# 05_Uart_Bluetooth.net
KiCad netlist of a schematic drawn in Altium Designer
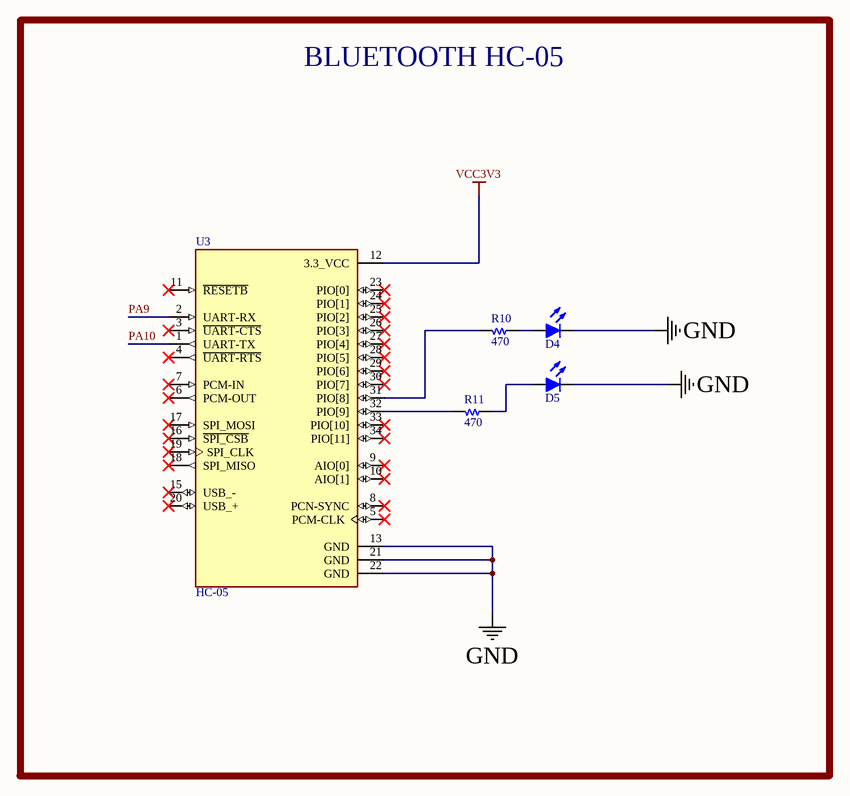
[diagram p0: 05_Uart_Bluetooth.SchDoc]

(export (version "E")
  (design (tool "Eeschema 10.0.6"))
  (components
    (comp (ref "D4")
      (value "Led")
      (footprint "Led 0805")
      (description "Typical LED")
      (libsource (lib "led") (part "Led"))
    )
    (comp (ref "D5")
      (value "Led")
      (footprint "Led 0805")
      (description "Typical LED")
      (libsource (lib "led") (part "Led"))
    )
    (comp (ref "R10")
      (value "470")
      (footprint "R 0805")
      (description "Resistor")
      (libsource (lib "chipfc_libs") (part "Resistor"))
    )
    (comp (ref "R11")
      (value "470")
      (footprint "R 0805")
      (description "Resistor")
      (libsource (lib "chipfc_libs") (part "Resistor"))
    )
    (comp (ref "U3")
      (value "HC-05")
      (footprint "XCVR_HC-05")
      (description "Bluetooth to Serial Port Module")
      (libsource (lib "HC-05") (part "HC-05"))
    )
  )
  (nets
    (net (code "1") (name "/PA9") (class "Default")
      (node (ref "U3") (pin "2") (pinfunction "UART-RX_2") (pintype "input"))
    )
    (net (code "2") (name "/PA10") (class "Default")
      (node (ref "U3") (pin "1") (pinfunction "UART-TX_1") (pintype "output"))
    )
    (net (code "3") (name "GND") (class "Default")
      (node (ref "D4") (pin "2") (pinfunction "K_2") (pintype "passive"))
      (node (ref "D5") (pin "2") (pinfunction "K_2") (pintype "passive"))
      (node (ref "U3") (pin "13") (pinfunction "GND_13") (pintype "power_in"))
      (node (ref "U3") (pin "21") (pinfunction "GND_21") (pintype "power_in"))
      (node (ref "U3") (pin "22") (pinfunction "GND_22") (pintype "power_in"))
    )
    (net (code "4") (name "Net-(D4-A)") (class "Default")
      (node (ref "D4") (pin "1") (pinfunction "A_1") (pintype "passive"))
      (node (ref "R10") (pin "1") (pinfunction "1_1") (pintype "passive"))
    )
    (net (code "5") (name "Net-(D5-A)") (class "Default")
      (node (ref "D5") (pin "1") (pinfunction "A_1") (pintype "passive"))
      (node (ref "R11") (pin "1") (pinfunction "1_1") (pintype "passive"))
    )
    (net (code "6") (name "Net-(U3-PIO[8])") (class "Default")
      (node (ref "R10") (pin "2") (pinfunction "2_2") (pintype "passive"))
      (node (ref "U3") (pin "31") (pinfunction "PIO[8]_31") (pintype "bidirectional"))
    )
    (net (code "7") (name "Net-(U3-PIO[9])") (class "Default")
      (node (ref "R11") (pin "2") (pinfunction "2_2") (pintype "passive"))
      (node (ref "U3") (pin "32") (pinfunction "PIO[9]_32") (pintype "bidirectional"))
    )
    (net (code "8") (name "VCC3V3") (class "Default")
      (node (ref "U3") (pin "12") (pinfunction "3.3_VCC_12") (pintype "power_in"))
    )
    (net (code "9") (name "unconnected-(U3-AIO[0]-Pad9)") (class "Default")
      (node (ref "U3") (pin "9") (pinfunction "AIO[0]_9") (pintype "bidirectional+no_connect"))
    )
    (net (code "10") (name "unconnected-(U3-AIO[1]-Pad10)") (class "Default")
      (node (ref "U3") (pin "10") (pinfunction "AIO[1]_10") (pintype "bidirectional+no_connect"))
    )
    (net (code "11") (name "unconnected-(U3-PCM-CLK-Pad5)") (class "Default")
      (node (ref "U3") (pin "5") (pinfunction "PCM-CLK_5") (pintype "bidirectional+no_connect"))
    )
    (net (code "12") (name "unconnected-(U3-PCM-IN-Pad7)") (class "Default")
      (node (ref "U3") (pin "7") (pinfunction "PCM-IN_7") (pintype "input+no_connect"))
    )
    (net (code "13") (name "unconnected-(U3-PCM-OUT-Pad6)") (class "Default")
      (node (ref "U3") (pin "6") (pinfunction "PCM-OUT_6") (pintype "output+no_connect"))
    )
    (net (code "14") (name "unconnected-(U3-PCN-SYNC-Pad8)") (class "Default")
      (node (ref "U3") (pin "8") (pinfunction "PCN-SYNC_8") (pintype "bidirectional+no_connect"))
    )
    (net (code "15") (name "unconnected-(U3-PIO[0]-Pad23)") (class "Default")
      (node (ref "U3") (pin "23") (pinfunction "PIO[0]_23") (pintype "bidirectional+no_connect"))
    )
    (net (code "16") (name "unconnected-(U3-PIO[1]-Pad24)") (class "Default")
      (node (ref "U3") (pin "24") (pinfunction "PIO[1]_24") (pintype "bidirectional+no_connect"))
    )
    (net (code "17") (name "unconnected-(U3-PIO[2]-Pad25)") (class "Default")
      (node (ref "U3") (pin "25") (pinfunction "PIO[2]_25") (pintype "bidirectional+no_connect"))
    )
    (net (code "18") (name "unconnected-(U3-PIO[3]-Pad26)") (class "Default")
      (node (ref "U3") (pin "26") (pinfunction "PIO[3]_26") (pintype "bidirectional+no_connect"))
    )
    (net (code "19") (name "unconnected-(U3-PIO[4]-Pad27)") (class "Default")
      (node (ref "U3") (pin "27") (pinfunction "PIO[4]_27") (pintype "bidirectional+no_connect"))
    )
    (net (code "20") (name "unconnected-(U3-PIO[5]-Pad28)") (class "Default")
      (node (ref "U3") (pin "28") (pinfunction "PIO[5]_28") (pintype "bidirectional+no_connect"))
    )
    (net (code "21") (name "unconnected-(U3-PIO[6]-Pad29)") (class "Default")
      (node (ref "U3") (pin "29") (pinfunction "PIO[6]_29") (pintype "bidirectional+no_connect"))
    )
    (net (code "22") (name "unconnected-(U3-PIO[7]-Pad30)") (class "Default")
      (node (ref "U3") (pin "30") (pinfunction "PIO[7]_30") (pintype "bidirectional+no_connect"))
    )
    (net (code "23") (name "unconnected-(U3-PIO[10]-Pad33)") (class "Default")
      (node (ref "U3") (pin "33") (pinfunction "PIO[10]_33") (pintype "bidirectional+no_connect"))
    )
    (net (code "24") (name "unconnected-(U3-PIO[11]-Pad34)") (class "Default")
      (node (ref "U3") (pin "34") (pinfunction "PIO[11]_34") (pintype "bidirectional+no_connect"))
    )
    (net (code "25") (name "unconnected-(U3-SPI_CLK-Pad19)") (class "Default")
      (node (ref "U3") (pin "19") (pinfunction "SPI_CLK_19") (pintype "input+no_connect"))
    )
    (net (code "26") (name "unconnected-(U3-SPI_MISO-Pad18)") (class "Default")
      (node (ref "U3") (pin "18") (pinfunction "SPI_MISO_18") (pintype "output+no_connect"))
    )
    (net (code "27") (name "unconnected-(U3-SPI_MOSI-Pad17)") (class "Default")
      (node (ref "U3") (pin "17") (pinfunction "SPI_MOSI_17") (pintype "input+no_connect"))
    )
    (net (code "28") (name "unconnected-(U3-USB_+-Pad20)") (class "Default")
      (node (ref "U3") (pin "20") (pinfunction "USB_+_20") (pintype "bidirectional+no_connect"))
    )
    (net (code "29") (name "unconnected-(U3-USB_--Pad15)") (class "Default")
      (node (ref "U3") (pin "15") (pinfunction "USB_-_15") (pintype "bidirectional+no_connect"))
    )
    (net (code "30") (name "unconnected-(U3-~{RESETB}-Pad11)") (class "Default")
      (node (ref "U3") (pin "11") (pinfunction "~{RESETB}_11") (pintype "input+no_connect"))
    )
    (net (code "31") (name "unconnected-(U3-~{SPI_CSB}-Pad16)") (class "Default")
      (node (ref "U3") (pin "16") (pinfunction "~{SPI_CSB}_16") (pintype "input+no_connect"))
    )
    (net (code "32") (name "unconnected-(U3-~{UART-CTS}-Pad3)") (class "Default")
      (node (ref "U3") (pin "3") (pinfunction "~{UART-CTS}_3") (pintype "input+no_connect"))
    )
    (net (code "33") (name "unconnected-(U3-~{UART-RTS}-Pad4)") (class "Default")
      (node (ref "U3") (pin "4") (pinfunction "~{UART-RTS}_4") (pintype "output+no_connect"))
    )
  )
)
